# STRWHL-S03-V00-IsolatedCAN.net
KiCad netlist of a schematic drawn in Altium Designer
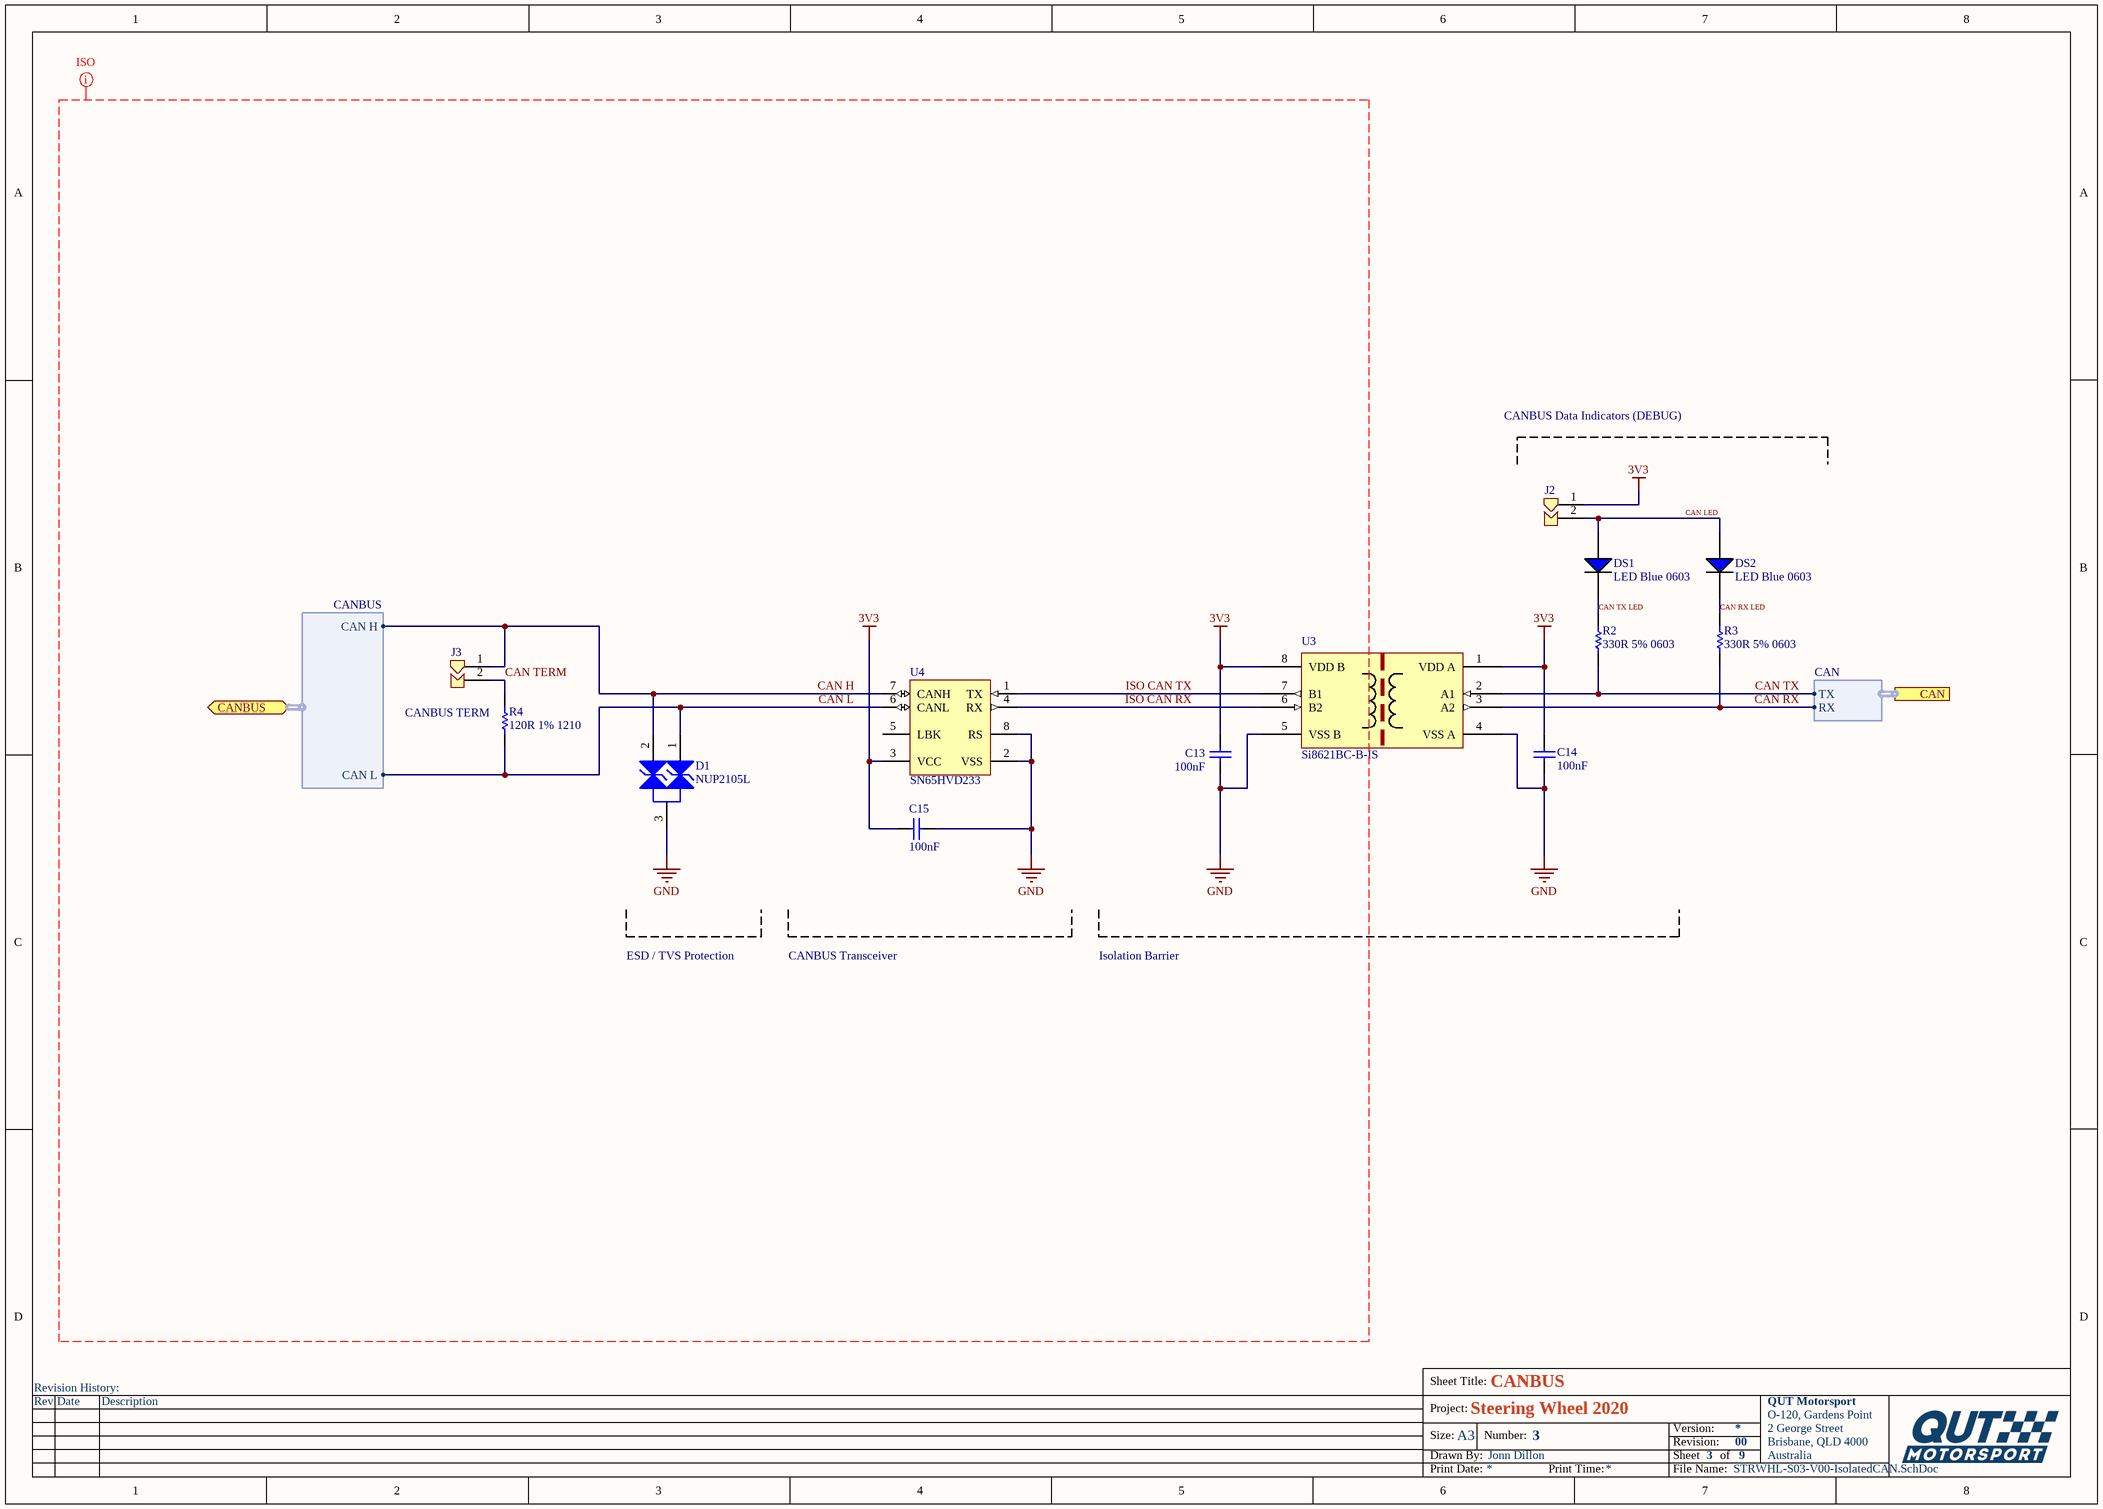
[diagram p0: STRWHL-S03-V00-IsolatedCAN.SchDoc]

(export (version "E")
  (design (tool "Eeschema 10.0.6"))
  (components
    (comp (ref "C13")
      (value "100nF")
      (footprint "Cap_Ceramic_0603")
      (description "Capacitor, Ceramic, SMD, 100nF, 50V, 5%, X7R, 0603")
      (libsource (lib "StandardCapacitors") (part "100nF 50V 5% X7R 0603"))
    )
    (comp (ref "C14")
      (value "100nF")
      (footprint "Cap_Ceramic_0603")
      (description "Capacitor, Ceramic, SMD, 100nF, 50V, 5%, X7R, 0603")
      (libsource (lib "StandardCapacitors") (part "100nF 50V 5% X7R 0603"))
    )
    (comp (ref "C15")
      (value "100nF")
      (footprint "Cap_Ceramic_0603")
      (description "Capacitor, Ceramic, SMD, 100nF, 50V, 5%, X7R, 0603")
      (libsource (lib "StandardCapacitors") (part "100nF 50V 5% X7R 0603"))
    )
    (comp (ref "D1")
      (value "NUP2105L")
      (footprint "NUP2105L")
      (libsource (lib "QUTMS_CANLibrary") (part "NUP2105L"))
    )
    (comp (ref "DS1")
      (value "LED Blue 0603")
      (footprint "LED BLUE 0603")
      (libsource (lib "QUTMS_LEDLibrary") (part "LED BLUE 0603"))
    )
    (comp (ref "DS2")
      (value "LED Blue 0603")
      (footprint "LED BLUE 0603")
      (libsource (lib "QUTMS_LEDLibrary") (part "LED BLUE 0603"))
    )
    (comp (ref "J2")
      (value "Jumper 2Way Solderable")
      (footprint "Jumper_2Way_Solderable")
      (description "Jumper 2Way Side Solderable")
      (libsource (lib "QUTMS_JumperLibrary") (part "Jumper 2Way Side Solderable"))
    )
    (comp (ref "J3")
      (value "Jumper 2Way Solderable")
      (footprint "Jumper_2Way_Solderable")
      (description "Jumper 2Way Side Solderable")
      (libsource (lib "QUTMS_JumperLibrary") (part "Jumper 2Way Side Solderable"))
    )
    (comp (ref "R2")
      (value "330R 5% 0603")
      (footprint "Res_ThinFilm_0603")
      (description "Resistor, SMD, 330R, 0.1W, 5%, 0603")
      (libsource (lib "StandardResistors") (part "330R 5% 0603"))
    )
    (comp (ref "R3")
      (value "330R 5% 0603")
      (footprint "Res_ThinFilm_0603")
      (description "Resistor, SMD, 330R, 0.1W, 5%, 0603")
      (libsource (lib "StandardResistors") (part "330R 5% 0603"))
    )
    (comp (ref "R4")
      (value "120R 1% 1210")
      (footprint "Res_ThinFilm_1210")
      (description "Resistor, SMD, 120R, 0.25W, 1%, 1210")
      (libsource (lib "StandardResistors") (part "120R 1% 1210"))
    )
    (comp (ref "U3")
      (value "Si8621BC-B-IS")
      (footprint "Si8621BC-B-IS")
      (libsource (lib "QUTMS_IsolatorLibrary") (part "Si8621BC-B-IS"))
    )
    (comp (ref "U4")
      (value "SN65HVD233")
      (footprint "SN65HVD233DR")
      (libsource (lib "QUTMS_CANLibrary") (part "SN65HVD233"))
    )
  )
  (nets
    (net (code "3") (name "/CAN H") (class "Default")
      (node (ref "D1") (pin "2") (pinfunction "2_2") (pintype "passive"))
      (node (ref "J3") (pin "1") (pinfunction "1_1") (pintype "passive"))
      (node (ref "U4") (pin "7") (pinfunction "CANH_7") (pintype "bidirectional"))
    )
    (net (code "4") (name "/CAN L") (class "Default")
      (node (ref "D1") (pin "1") (pinfunction "1_1") (pintype "passive"))
      (node (ref "R4") (pin "1") (pinfunction "1_1") (pintype "passive"))
      (node (ref "U4") (pin "6") (pinfunction "CANL_6") (pintype "bidirectional"))
    )
    (net (code "5") (name "/CAN LED") (class "Default")
      (node (ref "DS1") (pin "1") (pinfunction "A_1") (pintype "passive"))
      (node (ref "DS2") (pin "1") (pinfunction "A_1") (pintype "passive"))
      (node (ref "J2") (pin "2") (pinfunction "2_2") (pintype "passive"))
    )
    (net (code "6") (name "/CAN RX") (class "Default")
      (node (ref "R3") (pin "1") (pinfunction "1_1") (pintype "passive"))
      (node (ref "U3") (pin "3") (pinfunction "A2_3") (pintype "output"))
    )
    (net (code "7") (name "/CAN RX LED") (class "Default")
      (node (ref "DS2") (pin "2") (pinfunction "C_2") (pintype "passive"))
      (node (ref "R3") (pin "2") (pinfunction "2_2") (pintype "passive"))
    )
    (net (code "8") (name "/CAN TERM") (class "Default")
      (node (ref "J3") (pin "2") (pinfunction "2_2") (pintype "passive"))
      (node (ref "R4") (pin "2") (pinfunction "2_2") (pintype "passive"))
    )
    (net (code "9") (name "/CAN TX") (class "Default")
      (node (ref "R2") (pin "1") (pinfunction "1_1") (pintype "passive"))
      (node (ref "U3") (pin "2") (pinfunction "A1_2") (pintype "input"))
    )
    (net (code "10") (name "/CAN TX LED") (class "Default")
      (node (ref "DS1") (pin "2") (pinfunction "C_2") (pintype "passive"))
      (node (ref "R2") (pin "2") (pinfunction "2_2") (pintype "passive"))
    )
    (net (code "11") (name "/ISO CAN RX") (class "Default")
      (node (ref "U3") (pin "6") (pinfunction "B2_6") (pintype "input"))
      (node (ref "U4") (pin "4") (pinfunction "RX_4") (pintype "output"))
    )
    (net (code "12") (name "/ISO CAN TX") (class "Default")
      (node (ref "U3") (pin "7") (pinfunction "B1_7") (pintype "output"))
      (node (ref "U4") (pin "1") (pinfunction "TX_1") (pintype "input"))
    )
    (net (code "15") (name "3V3") (class "Default")
      (node (ref "C13") (pin "2") (pinfunction "2_2") (pintype "passive"))
      (node (ref "C14") (pin "2") (pinfunction "2_2") (pintype "passive"))
      (node (ref "C15") (pin "2") (pinfunction "2_2") (pintype "passive"))
      (node (ref "J2") (pin "1") (pinfunction "1_1") (pintype "passive"))
      (node (ref "U3") (pin "1") (pinfunction "VDD_A_1") (pintype "passive"))
      (node (ref "U3") (pin "8") (pinfunction "VDD_B_8") (pintype "passive"))
      (node (ref "U4") (pin "3") (pinfunction "VCC_3") (pintype "passive"))
    )
    (net (code "16") (name "GND") (class "Default")
      (node (ref "C13") (pin "1") (pinfunction "1_1") (pintype "passive"))
      (node (ref "C14") (pin "1") (pinfunction "1_1") (pintype "passive"))
      (node (ref "C15") (pin "1") (pinfunction "1_1") (pintype "passive"))
      (node (ref "D1") (pin "3") (pinfunction "3_3") (pintype "passive"))
      (node (ref "U3") (pin "4") (pinfunction "VSS_A_4") (pintype "passive"))
      (node (ref "U3") (pin "5") (pinfunction "VSS_B_5") (pintype "passive"))
      (node (ref "U4") (pin "2") (pinfunction "VSS_2") (pintype "passive"))
      (node (ref "U4") (pin "8") (pinfunction "RS_8") (pintype "passive"))
    )
    (net (code "17") (name "unconnected-(U4-LBK-Pad5)") (class "Default")
      (node (ref "U4") (pin "5") (pinfunction "LBK_5") (pintype "passive"))
    )
  )
)
